# Schematic_Final.net
KiCad netlist of a schematic drawn in EAGLE
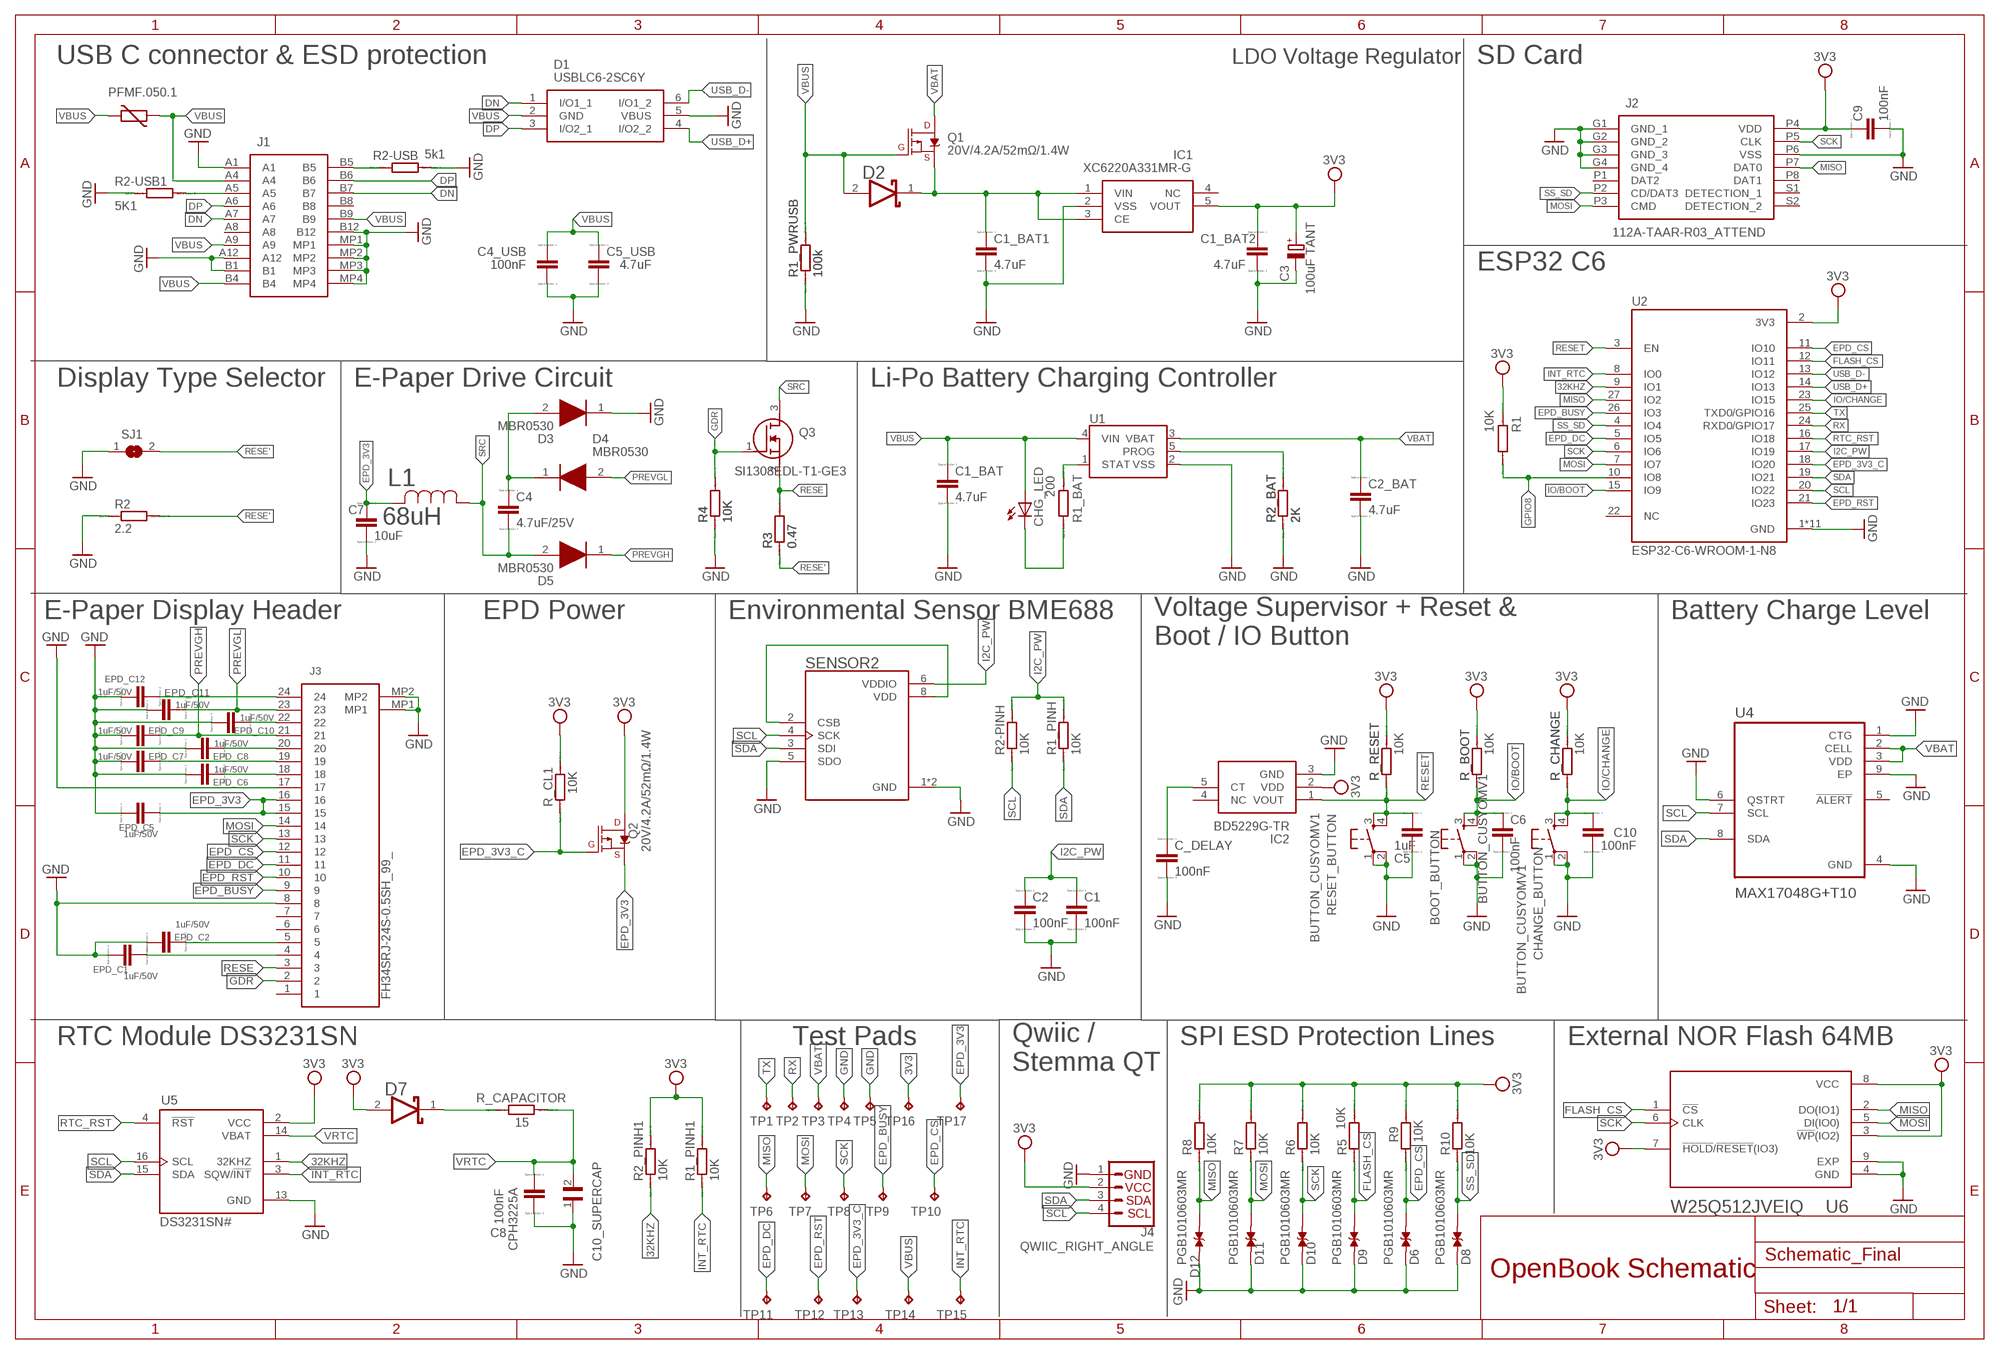
[diagram p0: schematic, sheet 1]

(export (version "E")
  (design (tool "Eeschema 10.0.6"))
  (components
    (comp (ref "BOOT_BUTTON")
      (value "BUTTON_CUSYOMV1")
      (footprint "eagle-import:MYBUTTON")
      (libsource (lib "eagle-import") (part "BUTTON_CUSYOMV1"))
    )
    (comp (ref "C1")
      (value "100nF")
      (footprint "eagle-import:ESP32_WROVER_EAGLE-LTSPICE_C0402")
      (libsource (lib "eagle-import") (part "ESP32_WROVER_EAGLE-LTSPICE_CC0402"))
    )
    (comp (ref "C1_BAT")
      (value "4.7uF")
      (footprint "eagle-import:ESP32_WROVER_EAGLE-LTSPICE_C0402")
      (libsource (lib "eagle-import") (part "ESP32_WROVER_EAGLE-LTSPICE_CC0402"))
    )
    (comp (ref "C1_BAT1")
      (value "4.7uF")
      (footprint "eagle-import:ESP32_WROVER_EAGLE-LTSPICE_C0402")
      (libsource (lib "eagle-import") (part "ESP32_WROVER_EAGLE-LTSPICE_CC0402"))
    )
    (comp (ref "C1_BAT2")
      (value "4.7uF")
      (footprint "eagle-import:ESP32_WROVER_EAGLE-LTSPICE_C0402")
      (libsource (lib "eagle-import") (part "ESP32_WROVER_EAGLE-LTSPICE_CC0402"))
    )
    (comp (ref "C2")
      (value "100nF")
      (footprint "eagle-import:ESP32_WROVER_EAGLE-LTSPICE_C0402")
      (libsource (lib "eagle-import") (part "ESP32_WROVER_EAGLE-LTSPICE_CC0402"))
    )
    (comp (ref "C2_BAT")
      (value "4.7uF")
      (footprint "eagle-import:ESP32_WROVER_EAGLE-LTSPICE_C0402")
      (libsource (lib "eagle-import") (part "ESP32_WROVER_EAGLE-LTSPICE_CC0402"))
    )
    (comp (ref "C3")
      (value "100uF TANT")
      (footprint "eagle-import:RCL_CT3528")
      (libsource (lib "eagle-import") (part "RCL_CPOL-EUCT3528"))
    )
    (comp (ref "C4")
      (value "4.7uF/25V")
      (footprint "eagle-import:ESP32_WROVER_EAGLE-LTSPICE_C0402")
      (libsource (lib "eagle-import") (part "ESP32_WROVER_EAGLE-LTSPICE_CC0402"))
    )
    (comp (ref "C4_USB")
      (value "100nF")
      (footprint "eagle-import:ESP32_WROVER_EAGLE-LTSPICE_C0402")
      (libsource (lib "eagle-import") (part "ESP32_WROVER_EAGLE-LTSPICE_CC0402"))
    )
    (comp (ref "C5")
      (value "1uF")
      (footprint "eagle-import:ESP32_WROVER_EAGLE-LTSPICE_C0402")
      (libsource (lib "eagle-import") (part "ESP32_WROVER_EAGLE-LTSPICE_CC0402"))
    )
    (comp (ref "C5_USB")
      (value "4.7uF")
      (footprint "eagle-import:ESP32_WROVER_EAGLE-LTSPICE_C0402")
      (libsource (lib "eagle-import") (part "ESP32_WROVER_EAGLE-LTSPICE_CC0402"))
    )
    (comp (ref "C6")
      (value "100nF")
      (footprint "eagle-import:ESP32_WROVER_EAGLE-LTSPICE_C0402")
      (libsource (lib "eagle-import") (part "ESP32_WROVER_EAGLE-LTSPICE_CC0402"))
    )
    (comp (ref "C7")
      (value "10uF")
      (footprint "eagle-import:ESP32_WROVER_EAGLE-LTSPICE_C0402")
      (libsource (lib "eagle-import") (part "ESP32_WROVER_EAGLE-LTSPICE_CC0402"))
    )
    (comp (ref "C8")
      (value "100nF")
      (footprint "eagle-import:ESP32_WROVER_EAGLE-LTSPICE_C0402")
      (libsource (lib "eagle-import") (part "ESP32_WROVER_EAGLE-LTSPICE_CC0402"))
    )
    (comp (ref "C9")
      (value "100nF")
      (footprint "eagle-import:ESP32_WROVER_EAGLE-LTSPICE_C0402")
      (libsource (lib "eagle-import") (part "ESP32_WROVER_EAGLE-LTSPICE_CC0402"))
    )
    (comp (ref "C10")
      (value "100nF")
      (footprint "eagle-import:ESP32_WROVER_EAGLE-LTSPICE_C0402")
      (libsource (lib "eagle-import") (part "ESP32_WROVER_EAGLE-LTSPICE_CC0402"))
    )
    (comp (ref "C10_SUPERCAP")
      (value "CPH3225A")
      (footprint "eagle-import:CAPCP3225X100N")
      (fields (field (name "MF") "Seiko Instruments"))
      (libsource (lib "eagle-import") (part "CPH3225A"))
    )
    (comp (ref "CHANGE_BUTTON")
      (value "BUTTON_CUSYOMV1")
      (footprint "eagle-import:MYBUTTON")
      (libsource (lib "eagle-import") (part "BUTTON_CUSYOMV1"))
    )
    (comp (ref "CHG_LED")
      (value "ADAFRUIT_LEDCHIP-LED0603")
      (footprint "eagle-import:ADAFRUIT_CHIP-LED0603")
      (libsource (lib "eagle-import") (part "ADAFRUIT_LEDCHIP-LED0603"))
    )
    (comp (ref "C_DELAY")
      (value "100nF")
      (footprint "eagle-import:ESP32_WROVER_EAGLE-LTSPICE_C0402")
      (libsource (lib "eagle-import") (part "ESP32_WROVER_EAGLE-LTSPICE_CC0402"))
    )
    (comp (ref "D1")
      (value "USBLC6-2SC6Y")
      (footprint "eagle-import:SOT95P280X145-6N")
      (fields (field (name "MF") "STMicroelectronics"))
      (libsource (lib "eagle-import") (part "USBLC6-2SC6Y"))
    )
    (comp (ref "D2")
      (value "ESP32_WROVER_AVX---SD0805S020S1R0_AVX_SD0805S020S1R0_0_0AVX_SD0805S020S1R0_0_0")
      (footprint "eagle-import:ESP32_WROVER_AVX---SD0805S020S1R0_AVX_SD0805S020S1R0_0")
      (fields
        (field (name "DIGIKEY_PART_NUMBER") "478-7800-1-ND")
        (field (name "MF") "AVX")
        (field (name "MOUSER_PART_NUMBER") "581-SD0805S020S1R0")
      )
      (libsource (lib "eagle-import") (part "ESP32_WROVER_AVX---SD0805S020S1R0_AVX_SD0805S020S1R0_0_0AVX_SD0805S020S1R0_0_0"))
    )
    (comp (ref "D3")
      (value "MBR0530")
      (footprint "eagle-import:SOD3716X135N")
      (fields (field (name "MF") "ON Semiconductor"))
      (libsource (lib "eagle-import") (part "MBR0530"))
    )
    (comp (ref "D4")
      (value "MBR0530")
      (footprint "eagle-import:SOD3716X135N")
      (fields (field (name "MF") "ON Semiconductor"))
      (libsource (lib "eagle-import") (part "MBR0530"))
    )
    (comp (ref "D5")
      (value "MBR0530")
      (footprint "eagle-import:SOD3716X135N")
      (fields (field (name "MF") "ON Semiconductor"))
      (libsource (lib "eagle-import") (part "MBR0530"))
    )
    (comp (ref "D6")
      (value "PGB1010603MR")
      (footprint "eagle-import:DIOC1608X36N")
      (fields (field (name "MF") "Littelfuse Inc."))
      (libsource (lib "eagle-import") (part "PGB1010603MR"))
    )
    (comp (ref "D7")
      (value "ESP32_WROVER_AVX---SD0805S020S1R0_AVX_SD0805S020S1R0_0_0AVX_SD0805S020S1R0_0_0")
      (footprint "eagle-import:ESP32_WROVER_AVX---SD0805S020S1R0_AVX_SD0805S020S1R0_0")
      (fields
        (field (name "DIGIKEY_PART_NUMBER") "478-7800-1-ND")
        (field (name "MF") "AVX")
        (field (name "MOUSER_PART_NUMBER") "581-SD0805S020S1R0")
      )
      (libsource (lib "eagle-import") (part "DeskAssistant v19 v1_vf.bE1N5c7jRn-k-Y7_dsTgZA_ESP32_WROVER_AVX---SD0805S020S1R0_AVX_SD0805S020S1R0_0_0AVX_SD0805S020S1R0_0_0"))
    )
    (comp (ref "D8")
      (value "PGB1010603MR")
      (footprint "eagle-import:DIOC1608X36N")
      (fields (field (name "MF") "Littelfuse Inc."))
      (libsource (lib "eagle-import") (part "PGB1010603MR"))
    )
    (comp (ref "D9")
      (value "PGB1010603MR")
      (footprint "eagle-import:DIOC1608X36N")
      (fields (field (name "MF") "Littelfuse Inc."))
      (libsource (lib "eagle-import") (part "PGB1010603MR"))
    )
    (comp (ref "D10")
      (value "PGB1010603MR")
      (footprint "eagle-import:DIOC1608X36N")
      (fields (field (name "MF") "Littelfuse Inc."))
      (libsource (lib "eagle-import") (part "PGB1010603MR"))
    )
    (comp (ref "D11")
      (value "PGB1010603MR")
      (footprint "eagle-import:DIOC1608X36N")
      (fields (field (name "MF") "Littelfuse Inc."))
      (libsource (lib "eagle-import") (part "PGB1010603MR"))
    )
    (comp (ref "D12")
      (value "PGB1010603MR")
      (footprint "eagle-import:DIOC1608X36N")
      (fields (field (name "MF") "Littelfuse Inc."))
      (libsource (lib "eagle-import") (part "PGB1010603MR"))
    )
    (comp (ref "EPD_C1")
      (value "1uF/50V")
      (footprint "eagle-import:ESP32_WROVER_EAGLE-LTSPICE_C0402")
      (libsource (lib "eagle-import") (part "ESP32_WROVER_EAGLE-LTSPICE_CC0402"))
    )
    (comp (ref "EPD_C2")
      (value "1uF/50V")
      (footprint "eagle-import:ESP32_WROVER_EAGLE-LTSPICE_C0402")
      (libsource (lib "eagle-import") (part "ESP32_WROVER_EAGLE-LTSPICE_CC0402"))
    )
    (comp (ref "EPD_C5")
      (value "1uF/50V")
      (footprint "eagle-import:ESP32_WROVER_EAGLE-LTSPICE_C0402")
      (libsource (lib "eagle-import") (part "ESP32_WROVER_EAGLE-LTSPICE_CC0402"))
    )
    (comp (ref "EPD_C6")
      (value "1uF/50V")
      (footprint "eagle-import:ESP32_WROVER_EAGLE-LTSPICE_C0402")
      (libsource (lib "eagle-import") (part "ESP32_WROVER_EAGLE-LTSPICE_CC0402"))
    )
    (comp (ref "EPD_C7")
      (value "1uF/50V")
      (footprint "eagle-import:ESP32_WROVER_EAGLE-LTSPICE_C0402")
      (libsource (lib "eagle-import") (part "ESP32_WROVER_EAGLE-LTSPICE_CC0402"))
    )
    (comp (ref "EPD_C8")
      (value "1uF/50V")
      (footprint "eagle-import:ESP32_WROVER_EAGLE-LTSPICE_C0402")
      (libsource (lib "eagle-import") (part "ESP32_WROVER_EAGLE-LTSPICE_CC0402"))
    )
    (comp (ref "EPD_C9")
      (value "1uF/50V")
      (footprint "eagle-import:ESP32_WROVER_EAGLE-LTSPICE_C0402")
      (libsource (lib "eagle-import") (part "ESP32_WROVER_EAGLE-LTSPICE_CC0402"))
    )
    (comp (ref "EPD_C10")
      (value "1uF/50V")
      (footprint "eagle-import:ESP32_WROVER_EAGLE-LTSPICE_C0402")
      (libsource (lib "eagle-import") (part "ESP32_WROVER_EAGLE-LTSPICE_CC0402"))
    )
    (comp (ref "EPD_C11")
      (value "1uF/50V")
      (footprint "eagle-import:ESP32_WROVER_EAGLE-LTSPICE_C0402")
      (libsource (lib "eagle-import") (part "ESP32_WROVER_EAGLE-LTSPICE_CC0402"))
    )
    (comp (ref "EPD_C12")
      (value "1uF/50V")
      (footprint "eagle-import:ESP32_WROVER_EAGLE-LTSPICE_C0402")
      (libsource (lib "eagle-import") (part "ESP32_WROVER_EAGLE-LTSPICE_CC0402"))
    )
    (comp (ref "IC1")
      (value "XC6220A331MR-G")
      (footprint "eagle-import:SOT95P280X120-5N")
      (fields (field (name "MOUSER_PART_NUMBER") "865-XC6220A331MR-G"))
      (libsource (lib "eagle-import") (part "XC6220A331MR-G"))
    )
    (comp (ref "IC2")
      (value "BD5229G-TR")
      (footprint "eagle-import:SOT95P280X125-5N")
      (fields (field (name "MOUSER_PART_NUMBER") "755-BD5229G-TR"))
      (libsource (lib "eagle-import") (part "BD5229G-TR"))
    )
    (comp (ref "J1")
      (value "SAMACSYS_PARTS_USB4110-GF-A")
      (footprint "eagle-import:SAMACSYS_PARTS_USB4110GFA")
      (fields
        (field (name "MANUFACTURER_PART_NUMBER") "USB4110-GF-A")
        (field (name "MOUSER_PART_NUMBER") "640-USB4110-GF-A")
      )
      (libsource (lib "eagle-import") (part "SAMACSYS_PARTS_USB4110-GF-A"))
    )
    (comp (ref "J2")
      (value "112A-TAAR-R03_ATTEND")
      (footprint "eagle-import:112ATAARR03ATTEND")
      (fields (field (name "MANUFACTURER_PART_NUMBER") "112A-TAAR-R03 ATTEND"))
      (libsource (lib "eagle-import") (part "112A-TAAR-R03_ATTEND"))
    )
    (comp (ref "J3")
      (value "FH34SRJ-24S-0.5SH_99_")
      (footprint "eagle-import:FH34SRJ24S05SH99")
      (fields
        (field (name "MANUFACTURER_PART_NUMBER") "FH34SRJ-24S-0.5SH(99)")
        (field (name "MOUSER_PART_NUMBER") "798-FH34SRJ24S05SH99")
      )
      (libsource (lib "eagle-import") (part "FH34SRJ-24S-0.5SH_99_"))
    )
    (comp (ref "J4")
      (value "QWIIC_RIGHT_ANGLE")
      (footprint "eagle-import:JST04_1MM_RA")
      (libsource (lib "eagle-import") (part "QWIIC_CONNECTORJS-1MM"))
    )
    (comp (ref "L1")
      (value "68uH")
      (footprint "eagle-import:IND_4828-WE-TPC_WRE")
      (fields
        (field (name "MANUFACTURER_PART_NUMBER") "744043680")
        (field (name "COPYRIGHT") "Copyright (C) 2024 Ultra Librarian. All rights reserved.")
      )
      (libsource (lib "eagle-import") (part "744043680IND_4828-WE-TPC_WRE"))
    )
    (comp (ref "PFMF.050.1")
      (value "ESP32C6_VARISTORCN1812")
      (footprint "eagle-import:ESP32C6_VARISTOR_CT_CN1812")
      (libsource (lib "eagle-import") (part "ESP32C6_VARISTORCN1812"))
    )
    (comp (ref "Q1")
      (value "20V/4.2A/52mΩ/1.4W")
      (footprint "eagle-import:ESP32_WROVER_SPARKFUN-DISCRETESEMI_SOT23-3")
      (libsource (lib "eagle-import") (part "ESP32_WROVER_SPARKFUN-DISCRETESEMI_MOSFET_PCH-DMG2305UX-7"))
    )
    (comp (ref "Q2")
      (value "20V/4.2A/52mΩ/1.4W")
      (footprint "eagle-import:ESP32_WROVER_SPARKFUN-DISCRETESEMI_SOT23-3")
      (libsource (lib "eagle-import") (part "ESP32_WROVER_SPARKFUN-DISCRETESEMI_MOSFET_PCH-DMG2305UX-7"))
    )
    (comp (ref "Q3")
      (value "SI1308EDL-T1-GE3")
      (footprint "eagle-import:SOT65P210X110-3N")
      (fields (field (name "MF") "Vishay Siliconix"))
      (libsource (lib "eagle-import") (part "SI1308EDL-T1-GE3"))
    )
    (comp (ref "R1")
      (value "10K")
      (footprint "eagle-import:ESP32_WROVER_EAGLE-LTSPICE_R0402")
      (libsource (lib "eagle-import") (part "DeskAssistant v19 v1_vf.bE1N5c7jRn-k-Y7_dsTgZA_ESP32_WROVER_EAGLE-LTSPICE_RR0402"))
    )
    (comp (ref "R1_BAT")
      (value "200")
      (footprint "eagle-import:ESP32_WROVER_EAGLE-LTSPICE_R0402")
      (libsource (lib "eagle-import") (part "DeskAssistant v19 v1_vf.bE1N5c7jRn-k-Y7_dsTgZA_ESP32_WROVER_EAGLE-LTSPICE_RR0402"))
    )
    (comp (ref "R1_PINH")
      (value "10K")
      (footprint "eagle-import:ESP32_WROVER_EAGLE-LTSPICE_R0402")
      (libsource (lib "eagle-import") (part "DeskAssistant v19 v1_vf.bE1N5c7jRn-k-Y7_dsTgZA_ESP32_WROVER_EAGLE-LTSPICE_RR0402"))
    )
    (comp (ref "R1_PINH1")
      (value "10K")
      (footprint "eagle-import:ESP32_WROVER_EAGLE-LTSPICE_R0402")
      (libsource (lib "eagle-import") (part "DeskAssistant v19 v1_vf.bE1N5c7jRn-k-Y7_dsTgZA_ESP32_WROVER_EAGLE-LTSPICE_RR0402"))
    )
    (comp (ref "R1_PWRUSB")
      (value "100k")
      (footprint "eagle-import:ESP32_WROVER_EAGLE-LTSPICE_R0402")
      (libsource (lib "eagle-import") (part "DeskAssistant v19 v1_vf.bE1N5c7jRn-k-Y7_dsTgZA_ESP32_WROVER_EAGLE-LTSPICE_RR0402"))
    )
    (comp (ref "R2")
      (value "2.2")
      (footprint "eagle-import:ESP32_WROVER_EAGLE-LTSPICE_R0402")
      (libsource (lib "eagle-import") (part "DeskAssistant v19 v1_vf.bE1N5c7jRn-k-Y7_dsTgZA_ESP32_WROVER_EAGLE-LTSPICE_RR0402"))
    )
    (comp (ref "R2-PINH")
      (value "10K")
      (footprint "eagle-import:ESP32_WROVER_EAGLE-LTSPICE_R0402")
      (libsource (lib "eagle-import") (part "DeskAssistant v19 v1_vf.bE1N5c7jRn-k-Y7_dsTgZA_ESP32_WROVER_EAGLE-LTSPICE_RR0402"))
    )
    (comp (ref "R2-USB")
      (value "5k1")
      (footprint "eagle-import:ESP32_WROVER_EAGLE-LTSPICE_R0402")
      (libsource (lib "eagle-import") (part "ESP32_WROVER_EAGLE-LTSPICE_RR0402"))
    )
    (comp (ref "R2-USB1")
      (value "5K1")
      (footprint "eagle-import:ESP32_WROVER_EAGLE-LTSPICE_R0402")
      (libsource (lib "eagle-import") (part "ESP32_WROVER_EAGLE-LTSPICE_RR0402"))
    )
    (comp (ref "R2_BAT")
      (value "2K")
      (footprint "eagle-import:ESP32_WROVER_EAGLE-LTSPICE_R0402")
      (libsource (lib "eagle-import") (part "DeskAssistant v19 v1_vf.bE1N5c7jRn-k-Y7_dsTgZA_ESP32_WROVER_EAGLE-LTSPICE_RR0402"))
    )
    (comp (ref "R2_PINH1")
      (value "10K")
      (footprint "eagle-import:ESP32_WROVER_EAGLE-LTSPICE_R0402")
      (libsource (lib "eagle-import") (part "DeskAssistant v19 v1_vf.bE1N5c7jRn-k-Y7_dsTgZA_ESP32_WROVER_EAGLE-LTSPICE_RR0402"))
    )
    (comp (ref "R3")
      (value "0.47")
      (footprint "eagle-import:ESP32_WROVER_EAGLE-LTSPICE_R0402")
      (libsource (lib "eagle-import") (part "DeskAssistant v19 v1_vf.bE1N5c7jRn-k-Y7_dsTgZA_ESP32_WROVER_EAGLE-LTSPICE_RR0402"))
    )
    (comp (ref "R4")
      (value "10K")
      (footprint "eagle-import:ESP32_WROVER_EAGLE-LTSPICE_R0402")
      (libsource (lib "eagle-import") (part "DeskAssistant v19 v1_vf.bE1N5c7jRn-k-Y7_dsTgZA_ESP32_WROVER_EAGLE-LTSPICE_RR0402"))
    )
    (comp (ref "R5")
      (value "10K")
      (footprint "eagle-import:ESP32_WROVER_EAGLE-LTSPICE_R0402")
      (libsource (lib "eagle-import") (part "DeskAssistant v19 v1_vf.bE1N5c7jRn-k-Y7_dsTgZA_ESP32_WROVER_EAGLE-LTSPICE_RR0402"))
    )
    (comp (ref "R6")
      (value "10K")
      (footprint "eagle-import:ESP32_WROVER_EAGLE-LTSPICE_R0402")
      (libsource (lib "eagle-import") (part "DeskAssistant v19 v1_vf.bE1N5c7jRn-k-Y7_dsTgZA_ESP32_WROVER_EAGLE-LTSPICE_RR0402"))
    )
    (comp (ref "R7")
      (value "10K")
      (footprint "eagle-import:ESP32_WROVER_EAGLE-LTSPICE_R0402")
      (libsource (lib "eagle-import") (part "DeskAssistant v19 v1_vf.bE1N5c7jRn-k-Y7_dsTgZA_ESP32_WROVER_EAGLE-LTSPICE_RR0402"))
    )
    (comp (ref "R8")
      (value "10K")
      (footprint "eagle-import:ESP32_WROVER_EAGLE-LTSPICE_R0402")
      (libsource (lib "eagle-import") (part "DeskAssistant v19 v1_vf.bE1N5c7jRn-k-Y7_dsTgZA_ESP32_WROVER_EAGLE-LTSPICE_RR0402"))
    )
    (comp (ref "R9")
      (value "10K")
      (footprint "eagle-import:ESP32_WROVER_EAGLE-LTSPICE_R0402")
      (libsource (lib "eagle-import") (part "DeskAssistant v19 v1_vf.bE1N5c7jRn-k-Y7_dsTgZA_ESP32_WROVER_EAGLE-LTSPICE_RR0402"))
    )
    (comp (ref "R10")
      (value "10K")
      (footprint "eagle-import:ESP32_WROVER_EAGLE-LTSPICE_R0402")
      (libsource (lib "eagle-import") (part "DeskAssistant v19 v1_vf.bE1N5c7jRn-k-Y7_dsTgZA_ESP32_WROVER_EAGLE-LTSPICE_RR0402"))
    )
    (comp (ref "RESET_BUTTON")
      (value "BUTTON_CUSYOMV1")
      (footprint "eagle-import:MYBUTTON")
      (libsource (lib "eagle-import") (part "BUTTON_CUSYOMV1"))
    )
    (comp (ref "R_BOOT")
      (value "10K")
      (footprint "eagle-import:ESP32_WROVER_EAGLE-LTSPICE_R0402")
      (libsource (lib "eagle-import") (part "DeskAssistant v19 v1_vf.bE1N5c7jRn-k-Y7_dsTgZA_ESP32_WROVER_EAGLE-LTSPICE_RR0402"))
    )
    (comp (ref "R_CAPACITOR")
      (value "15")
      (footprint "eagle-import:ESP32_WROVER_EAGLE-LTSPICE_R0402")
      (libsource (lib "eagle-import") (part "DeskAssistant v19 v1_vf.bE1N5c7jRn-k-Y7_dsTgZA_ESP32_WROVER_EAGLE-LTSPICE_RR0402"))
    )
    (comp (ref "R_CHANGE")
      (value "10K")
      (footprint "eagle-import:ESP32_WROVER_EAGLE-LTSPICE_R0402")
      (libsource (lib "eagle-import") (part "DeskAssistant v19 v1_vf.bE1N5c7jRn-k-Y7_dsTgZA_ESP32_WROVER_EAGLE-LTSPICE_RR0402"))
    )
    (comp (ref "R_CL1")
      (value "10K")
      (footprint "eagle-import:ESP32_WROVER_EAGLE-LTSPICE_R0402")
      (libsource (lib "eagle-import") (part "DeskAssistant v19 v1_vf.bE1N5c7jRn-k-Y7_dsTgZA_ESP32_WROVER_EAGLE-LTSPICE_RR0402"))
    )
    (comp (ref "R_RESET")
      (value "10K")
      (footprint "eagle-import:ESP32_WROVER_EAGLE-LTSPICE_R0402")
      (libsource (lib "eagle-import") (part "DeskAssistant v19 v1_vf.bE1N5c7jRn-k-Y7_dsTgZA_ESP32_WROVER_EAGLE-LTSPICE_RR0402"))
    )
    (comp (ref "SENSOR2")
      (value "ESP32_WROVER_BME680_BME680")
      (footprint "eagle-import:ESP32_WROVER_BME680_PSON80P300X300X100-8N")
      (fields (field (name "MF") "Bosch Sensortec") (field (name "MP") "BME680"))
      (libsource (lib "eagle-import") (part "ESP32_WROVER_BME680_BME680"))
    )
    (comp (ref "SJ1") (value "SJ") (footprint "eagle-import:SJ") (libsource (lib "eagle-import") (part "SJ")))
    (comp (ref "TP1")
      (value "TPTP20R")
      (footprint "eagle-import:TP20R")
      (libsource (lib "eagle-import") (part "TPTP20R"))
    )
    (comp (ref "TP2")
      (value "TPTP20R")
      (footprint "eagle-import:TP20R")
      (libsource (lib "eagle-import") (part "TPTP20R"))
    )
    (comp (ref "TP3")
      (value "TPTP20R")
      (footprint "eagle-import:TP20R")
      (libsource (lib "eagle-import") (part "TPTP20R"))
    )
    (comp (ref "TP4")
      (value "TPTP20R")
      (footprint "eagle-import:TP20R")
      (libsource (lib "eagle-import") (part "TPTP20R"))
    )
    (comp (ref "TP5")
      (value "TPTP20R")
      (footprint "eagle-import:TP20R")
      (libsource (lib "eagle-import") (part "TPTP20R"))
    )
    (comp (ref "TP6")
      (value "TPTP20R")
      (footprint "eagle-import:TP20R")
      (libsource (lib "eagle-import") (part "TPTP20R"))
    )
    (comp (ref "TP7")
      (value "TPTP20R")
      (footprint "eagle-import:TP20R")
      (libsource (lib "eagle-import") (part "TPTP20R"))
    )
    (comp (ref "TP8")
      (value "TPTP20R")
      (footprint "eagle-import:TP20R")
      (libsource (lib "eagle-import") (part "TPTP20R"))
    )
    (comp (ref "TP9")
      (value "TPTP20R")
      (footprint "eagle-import:TP20R")
      (libsource (lib "eagle-import") (part "TPTP20R"))
    )
    (comp (ref "TP10")
      (value "TPTP20R")
      (footprint "eagle-import:TP20R")
      (libsource (lib "eagle-import") (part "TPTP20R"))
    )
    (comp (ref "TP11")
      (value "TPTP20R")
      (footprint "eagle-import:TP20R")
      (libsource (lib "eagle-import") (part "TPTP20R"))
    )
    (comp (ref "TP12")
      (value "TPTP20R")
      (footprint "eagle-import:TP20R")
      (libsource (lib "eagle-import") (part "TPTP20R"))
    )
    (comp (ref "TP13")
      (value "TPTP20R")
      (footprint "eagle-import:TP20R")
      (libsource (lib "eagle-import") (part "TPTP20R"))
    )
    (comp (ref "TP14")
      (value "TPTP20R")
      (footprint "eagle-import:TP20R")
      (libsource (lib "eagle-import") (part "TPTP20R"))
    )
    (comp (ref "TP15")
      (value "TPTP20R")
      (footprint "eagle-import:TP20R")
      (libsource (lib "eagle-import") (part "TPTP20R"))
    )
    (comp (ref "TP16")
      (value "TPTP20R")
      (footprint "eagle-import:TP20R")
      (libsource (lib "eagle-import") (part "TPTP20R"))
    )
    (comp (ref "TP17")
      (value "TPTP20R")
      (footprint "eagle-import:TP20R")
      (libsource (lib "eagle-import") (part "TPTP20R"))
    )
    (comp (ref "U1")
      (value "ESP32_WROVER_SPARKFUN-IC-POWER_MCP73831")
      (footprint "eagle-import:ESP32_WROVER_SPARKFUN-IC-POWER_SOT23-5")
      (libsource (lib "eagle-import") (part "ESP32_WROVER_SPARKFUN-IC-POWER_MCP73831"))
    )
    (comp (ref "U2")
      (value "ESP32-C6-WROOM-1-N8")
      (footprint "eagle-import:XCVR_ESP32-C6-WROOM-1-N8")
      (fields (field (name "MF") "Espressif Systems"))
      (libsource (lib "eagle-import") (part "ESP32-C6-WROOM-1-N8"))
    )
    (comp (ref "U4")
      (value "MAX17048G+T10")
      (footprint "eagle-import:SON50P200X200X80-9N")
      (fields (field (name "MF") "Analog Devices"))
      (libsource (lib "eagle-import") (part "MAX17048G+T10"))
    )
    (comp (ref "U5")
      (value "DS3231SN#")
      (footprint "eagle-import:SOIC127P1032X265-16N")
      (fields (field (name "MF") "Analog Devices"))
      (libsource (lib "eagle-import") (part "DS3231SN#"))
    )
    (comp (ref "U6")
      (value "W25Q512JVEIQ")
      (footprint "eagle-import:SON127P600X800X80-9N")
      (fields (field (name "MF") "Winbond Electronics"))
      (libsource (lib "eagle-import") (part "W25Q512JVEIQ"))
    )
  )
  (nets
    (net (code "1") (name "3V3") (class "Default")
      (node (ref "C1_BAT2") (pin "1") (pinfunction "1_1") (pintype "passive"))
      (node (ref "C3") (pin "+") (pinfunction "+_+") (pintype "passive"))
      (node (ref "C9") (pin "1") (pinfunction "1_1") (pintype "passive"))
      (node (ref "D7") (pin "2") (pinfunction "ANODE_2") (pintype "bidirectional"))
      (node (ref "IC1") (pin "5") (pinfunction "VOUT_5") (pintype "bidirectional"))
      (node (ref "IC2") (pin "2") (pinfunction "VDD_2") (pintype "bidirectional"))
      (node (ref "J2") (pin "P4") (pinfunction "VDD_P4") (pintype "bidirectional"))
      (node (ref "J4") (pin "2") (pinfunction "2_2") (pintype "power_in"))
      (node (ref "Q2") (pin "3") (pinfunction "D_3") (pintype "bidirectional"))
      (node (ref "R1") (pin "2") (pinfunction "2_2") (pintype "passive"))
      (node (ref "R10") (pin "2") (pinfunction "2_2") (pintype "passive"))
      (node (ref "R1_PINH1") (pin "2") (pinfunction "2_2") (pintype "passive"))
      (node (ref "R2_PINH1") (pin "2") (pinfunction "2_2") (pintype "passive"))
      (node (ref "R5") (pin "2") (pinfunction "2_2") (pintype "passive"))
      (node (ref "R6") (pin "2") (pinfunction "2_2") (pintype "passive"))
      (node (ref "R7") (pin "2") (pinfunction "2_2") (pintype "passive"))
      (node (ref "R8") (pin "2") (pinfunction "2_2") (pintype "passive"))
      (node (ref "R9") (pin "2") (pinfunction "2_2") (pintype "passive"))
      (node (ref "R_BOOT") (pin "2") (pinfunction "2_2") (pintype "passive"))
      (node (ref "R_CHANGE") (pin "2") (pinfunction "2_2") (pintype "passive"))
      (node (ref "R_CL1") (pin "2") (pinfunction "2_2") (pintype "passive"))
      (node (ref "R_RESET") (pin "2") (pinfunction "2_2") (pintype "passive"))
      (node (ref "TP16") (pin "TP") (pinfunction "TP_TP") (pintype "input"))
      (node (ref "U2") (pin "2") (pinfunction "3V3_2") (pintype "power_in"))
      (node (ref "U5") (pin "2") (pinfunction "VCC_2") (pintype "power_in"))
      (node (ref "U6") (pin "3") (pinfunction "~{WP}(IO2)_3") (pintype "bidirectional"))
      (node (ref "U6") (pin "7") (pinfunction "~{HOLD}/~{RESET}(IO3)_7") (pintype "bidirectional"))
      (node (ref "U6") (pin "8") (pinfunction "VCC_8") (pintype "power_in"))
    )
    (net (code "2") (name "32KHZ") (class "Default")
      (node (ref "R2_PINH1") (pin "1") (pinfunction "1_1") (pintype "passive"))
      (node (ref "U2") (pin "9") (pinfunction "IO1_9") (pintype "bidirectional"))
      (node (ref "U5") (pin "1") (pinfunction "32KHZ_1") (pintype "output"))
    )
    (net (code "3") (name "DN") (class "Default")
      (node (ref "D1") (pin "1") (pinfunction "I/O1_1_1") (pintype "bidirectional"))
      (node (ref "J1") (pin "A7") (pinfunction "A7_A7") (pintype "bidirectional"))
      (node (ref "J1") (pin "B7") (pinfunction "B7_B7") (pintype "bidirectional"))
    )
    (net (code "4") (name "DP") (class "Default")
      (node (ref "D1") (pin "3") (pinfunction "I/O2_1_3") (pintype "bidirectional"))
      (node (ref "J1") (pin "A6") (pinfunction "A6_A6") (pintype "bidirectional"))
      (node (ref "J1") (pin "B6") (pinfunction "B6_B6") (pintype "bidirectional"))
    )
    (net (code "5") (name "EPD_3V3") (class "Default")
      (node (ref "C7") (pin "1") (pinfunction "1_1") (pintype "passive"))
      (node (ref "EPD_C5") (pin "2") (pinfunction "2_2") (pintype "passive"))
      (node (ref "J3") (pin "15") (pinfunction "15_15") (pintype "bidirectional"))
      (node (ref "J3") (pin "16") (pinfunction "16_16") (pintype "bidirectional"))
      (node (ref "L1") (pin "2") (pinfunction "2_2") (pintype "passive"))
      (node (ref "Q2") (pin "2") (pinfunction "S_2") (pintype "bidirectional"))
      (node (ref "TP17") (pin "TP") (pinfunction "TP_TP") (pintype "input"))
    )
    (net (code "6") (name "EPD_3V3_C") (class "Default")
      (node (ref "Q2") (pin "1") (pinfunction "G_1") (pintype "bidirectional"))
      (node (ref "R_CL1") (pin "1") (pinfunction "1_1") (pintype "passive"))
      (node (ref "TP13") (pin "TP") (pinfunction "TP_TP") (pintype "input"))
      (node (ref "U2") (pin "18") (pinfunction "IO20_18") (pintype "bidirectional"))
    )
    (net (code "7") (name "EPD_BUSY") (class "Default")
      (node (ref "J3") (pin "9") (pinfunction "9_9") (pintype "bidirectional"))
      (node (ref "TP9") (pin "TP") (pinfunction "TP_TP") (pintype "input"))
      (node (ref "U2") (pin "26") (pinfunction "IO3_26") (pintype "bidirectional"))
    )
    (net (code "8") (name "EPD_CS") (class "Default")
      (node (ref "D6") (pin "2") (pinfunction "2_2") (pintype "passive"))
      (node (ref "J3") (pin "12") (pinfunction "12_12") (pintype "bidirectional"))
      (node (ref "R9") (pin "1") (pinfunction "1_1") (pintype "passive"))
      (node (ref "TP10") (pin "TP") (pinfunction "TP_TP") (pintype "input"))
      (node (ref "U2") (pin "11") (pinfunction "IO10_11") (pintype "bidirectional"))
    )
    (net (code "9") (name "EPD_DC") (class "Default")
      (node (ref "J3") (pin "11") (pinfunction "11_11") (pintype "bidirectional"))
      (node (ref "TP11") (pin "TP") (pinfunction "TP_TP") (pintype "input"))
      (node (ref "U2") (pin "5") (pinfunction "IO5_5") (pintype "bidirectional"))
    )
    (net (code "10") (name "EPD_RST") (class "Default")
      (node (ref "J3") (pin "10") (pinfunction "10_10") (pintype "bidirectional"))
      (node (ref "TP12") (pin "TP") (pinfunction "TP_TP") (pintype "input"))
      (node (ref "U2") (pin "21") (pinfunction "IO23_21") (pintype "bidirectional"))
    )
    (net (code "11") (name "FLASH_CS") (class "Default")
      (node (ref "D9") (pin "2") (pinfunction "2_2") (pintype "passive"))
      (node (ref "R5") (pin "1") (pinfunction "1_1") (pintype "passive"))
      (node (ref "U2") (pin "12") (pinfunction "IO11_12") (pintype "bidirectional"))
      (node (ref "U6") (pin "1") (pinfunction "~{CS}_1") (pintype "input"))
    )
    (net (code "12") (name "GDR") (class "Default")
      (node (ref "J3") (pin "2") (pinfunction "2_2") (pintype "bidirectional"))
      (node (ref "Q3") (pin "1") (pinfunction "G_1") (pintype "bidirectional"))
      (node (ref "R4") (pin "2") (pinfunction "2_2") (pintype "passive"))
    )
    (net (code "13") (name "GND") (class "Default")
      (node (ref "BOOT_BUTTON") (pin "1") (pinfunction "1_1") (pintype "passive"))
      (node (ref "BOOT_BUTTON") (pin "2") (pinfunction "2_2") (pintype "passive"))
      (node (ref "C1") (pin "2") (pinfunction "2_2") (pintype "passive"))
      (node (ref "C10") (pin "2") (pinfunction "2_2") (pintype "passive"))
      (node (ref "C10_SUPERCAP") (pin "1") (pinfunction "1_1") (pintype "passive"))
      (node (ref "C1_BAT") (pin "2") (pinfunction "2_2") (pintype "passive"))
      (node (ref "C1_BAT1") (pin "2") (pinfunction "2_2") (pintype "passive"))
      (node (ref "C1_BAT2") (pin "2") (pinfunction "2_2") (pintype "passive"))
      (node (ref "C2") (pin "2") (pinfunction "2_2") (pintype "passive"))
      (node (ref "C2_BAT") (pin "2") (pinfunction "2_2") (pintype "passive"))
      (node (ref "C3") (pin "-") (pinfunction "-_-") (pintype "passive"))
      (node (ref "C4_USB") (pin "2") (pinfunction "2_2") (pintype "passive"))
      (node (ref "C5") (pin "2") (pinfunction "2_2") (pintype "passive"))
      (node (ref "C5_USB") (pin "2") (pinfunction "2_2") (pintype "passive"))
      (node (ref "C6") (pin "2") (pinfunction "2_2") (pintype "passive"))
      (node (ref "C7") (pin "2") (pinfunction "2_2") (pintype "passive"))
      (node (ref "C8") (pin "2") (pinfunction "2_2") (pintype "passive"))
      (node (ref "C9") (pin "2") (pinfunction "2_2") (pintype "passive"))
      (node (ref "CHANGE_BUTTON") (pin "1") (pinfunction "1_1") (pintype "passive"))
      (node (ref "CHANGE_BUTTON") (pin "2") (pinfunction "2_2") (pintype "passive"))
      (node (ref "C_DELAY") (pin "2") (pinfunction "2_2") (pintype "passive"))
      (node (ref "D1") (pin "5") (pinfunction "VBUS_5") (pintype "bidirectional"))
      (node (ref "D10") (pin "1") (pinfunction "1_1") (pintype "passive"))
      (node (ref "D11") (pin "1") (pinfunction "1_1") (pintype "passive"))
      (node (ref "D12") (pin "1") (pinfunction "1_1") (pintype "passive"))
      (node (ref "D3") (pin "1") (pinfunction "K_1") (pintype "bidirectional"))
      (node (ref "D6") (pin "1") (pinfunction "1_1") (pintype "passive"))
      (node (ref "D8") (pin "1") (pinfunction "1_1") (pintype "passive"))
      (node (ref "D9") (pin "1") (pinfunction "1_1") (pintype "passive"))
      (node (ref "EPD_C1") (pin "1") (pinfunction "1_1") (pintype "passive"))
      (node (ref "EPD_C10") (pin "1") (pinfunction "1_1") (pintype "passive"))
      (node (ref "EPD_C11") (pin "1") (pinfunction "1_1") (pintype "passive"))
      (node (ref "EPD_C12") (pin "1") (pinfunction "1_1") (pintype "passive"))
      (node (ref "EPD_C2") (pin "1") (pinfunction "1_1") (pintype "passive"))
      (node (ref "EPD_C5") (pin "1") (pinfunction "1_1") (pintype "passive"))
      (node (ref "EPD_C6") (pin "1") (pinfunction "1_1") (pintype "passive"))
      (node (ref "EPD_C7") (pin "1") (pinfunction "1_1") (pintype "passive"))
      (node (ref "EPD_C8") (pin "1") (pinfunction "1_1") (pintype "passive"))
      (node (ref "EPD_C9") (pin "1") (pinfunction "1_1") (pintype "passive"))
      (node (ref "IC1") (pin "2") (pinfunction "VSS_2") (pintype "bidirectional"))
      (node (ref "IC2") (pin "3") (pinfunction "GND_3") (pintype "bidirectional"))
      (node (ref "J1") (pin "A1") (pinfunction "A1_A1") (pintype "bidirectional"))
      (node (ref "J1") (pin "A12") (pinfunction "A12_A12") (pintype "bidirectional"))
      (node (ref "J1") (pin "B1") (pinfunction "B1_B1") (pintype "bidirectional"))
      (node (ref "J1") (pin "B12") (pinfunction "B12_B12") (pintype "bidirectional"))
      (node (ref "J1") (pin "MP1") (pinfunction "MP1_MP1") (pintype "bidirectional"))
      (node (ref "J1") (pin "MP2") (pinfunction "MP2_MP2") (pintype "bidirectional"))
      (node (ref "J1") (pin "MP3") (pinfunction "MP3_MP3") (pintype "bidirectional"))
      (node (ref "J1") (pin "MP4") (pinfunction "MP4_MP4") (pintype "bidirectional"))
      (node (ref "J2") (pin "G1") (pinfunction "GND_1_G1") (pintype "bidirectional"))
      (node (ref "J2") (pin "G2") (pinfunction "GND_2_G2") (pintype "bidirectional"))
      (node (ref "J2") (pin "G3") (pinfunction "GND_3_G3") (pintype "bidirectional"))
      (node (ref "J2") (pin "G4") (pinfunction "GND_4_G4") (pintype "bidirectional"))
      (node (ref "J2") (pin "P6") (pinfunction "VSS_P6") (pintype "bidirectional"))
      (node (ref "J3") (pin "17") (pinfunction "17_17") (pintype "bidirectional"))
      (node (ref "J3") (pin "8") (pinfunction "8_8") (pintype "bidirectional"))
      (node (ref "J3") (pin "MP1") (pinfunction "MP1_MP1") (pintype "bidirectional"))
      (node (ref "J3") (pin "MP2") (pinfunction "MP2_MP2") (pintype "bidirectional"))
      (node (ref "J4") (pin "1") (pinfunction "1_1") (pintype "power_in"))
      (node (ref "R1_PWRUSB") (pin "1") (pinfunction "1_1") (pintype "passive"))
      (node (ref "R2") (pin "1") (pinfunction "1_1") (pintype "passive"))
      (node (ref "R2-USB") (pin "2") (pinfunction "2_2") (pintype "passive"))
      (node (ref "R2-USB1") (pin "1") (pinfunction "1_1") (pintype "passive"))
      (node (ref "R2_BAT") (pin "1") (pinfunction "1_1") (pintype "passive"))
      (node (ref "R4") (pin "1") (pinfunction "1_1") (pintype "passive"))
      (node (ref "RESET_BUTTON") (pin "1") (pinfunction "1_1") (pintype "passive"))
      (node (ref "RESET_BUTTON") (pin "2") (pinfunction "2_2") (pintype "passive"))
      (node (ref "SENSOR2") (pin "1") (pinfunction "GND_1") (pintype "power_in"))
      (node (ref "SENSOR2") (pin "5") (pinfunction "SDO_5") (pintype "bidirectional"))
      (node (ref "SENSOR2") (pin "7") (pinfunction "GND_7") (pintype "power_in"))
      (node (ref "SJ1") (pin "1") (pinfunction "1_1") (pintype "passive"))
      (node (ref "TP4") (pin "TP") (pinfunction "TP_TP") (pintype "input"))
      (node (ref "TP5") (pin "TP") (pinfunction "TP_TP") (pintype "input"))
      (node (ref "U1") (pin "2") (pinfunction "VSS_2") (pintype "power_in"))
      (node (ref "U2") (pin "1") (pinfunction "GND_1") (pintype "power_in"))
      (node (ref "U2") (pin "28") (pinfunction "GND_28") (pintype "power_in"))
      (node (ref "U2") (pin "29_1") (pinfunction "GND_29_1") (pintype "power_in"))
      (node (ref "U2") (pin "29_2") (pinfunction "GND_29_2") (pintype "power_in"))
      (node (ref "U2") (pin "29_3") (pinfunction "GND_29_3") (pintype "power_in"))
      (node (ref "U2") (pin "29_4") (pinfunction "GND_29_4") (pintype "power_in"))
      (node (ref "U2") (pin "29_5") (pinfunction "GND_29_5") (pintype "power_in"))
      (node (ref "U2") (pin "29_6") (pinfunction "GND_29_6") (pintype "power_in"))
      (node (ref "U2") (pin "29_7") (pinfunction "GND_29_7") (pintype "power_in"))
      (node (ref "U2") (pin "29_8") (pinfunction "GND_29_8") (pintype "power_in"))
      (node (ref "U2") (pin "29_9") (pinfunction "GND_29_9") (pintype "power_in"))
      (node (ref "U4") (pin "1") (pinfunction "CTG_1") (pintype "power_in"))
      (node (ref "U4") (pin "4") (pinfunction "GND_4") (pintype "power_in"))
      (node (ref "U4") (pin "6") (pinfunction "QSTRT_6") (pintype "input"))
      (node (ref "U4") (pin "9") (pinfunction "EP_9") (pintype "power_in"))
      (node (ref "U5") (pin "13") (pinfunction "GND_13") (pintype "power_in"))
      (node (ref "U6") (pin "4") (pinfunction "GND_4") (pintype "power_in"))
      (node (ref "U6") (pin "9") (pinfunction "EXP_9") (pintype "passive"))
    )
    (net (code "14") (name "GPIO8") (class "Default")
      (node (ref "R1") (pin "1") (pinfunction "1_1") (pintype "passive"))
      (node (ref "U2") (pin "10") (pinfunction "IO8_10") (pintype "bidirectional"))
    )
    (net (code "15") (name "I2C_PW") (class "Default")
      (node (ref "C1") (pin "1") (pinfunction "1_1") (pintype "passive"))
      (node (ref "C2") (pin "1") (pinfunction "1_1") (pintype "passive"))
      (node (ref "R1_PINH") (pin "2") (pinfunction "2_2") (pintype "passive"))
      (node (ref "R2-PINH") (pin "2") (pinfunction "2_2") (pintype "passive"))
      (node (ref "SENSOR2") (pin "6") (pinfunction "VDDIO_6") (pintype "power_in"))
      (node (ref "U2") (pin "17") (pinfunction "IO19_17") (pintype "bidirectional"))
    )
    (net (code "16") (name "INT_RTC") (class "Default")
      (node (ref "R1_PINH1") (pin "1") (pinfunction "1_1") (pintype "passive"))
      (node (ref "TP15") (pin "TP") (pinfunction "TP_TP") (pintype "input"))
      (node (ref "U2") (pin "8") (pinfunction "IO0_8") (pintype "bidirectional"))
      (node (ref "U5") (pin "3") (pinfunction "SQW/~{INT}_3") (pintype "output"))
    )
    (net (code "17") (name "IO{slash}BOOT") (class "Default")
      (node (ref "BOOT_BUTTON") (pin "3") (pinfunction "3_3") (pintype "passive"))
      (node (ref "BOOT_BUTTON") (pin "4") (pinfunction "4_4") (pintype "passive"))
      (node (ref "C6") (pin "1") (pinfunction "1_1") (pintype "passive"))
      (node (ref "R_BOOT") (pin "1") (pinfunction "1_1") (pintype "passive"))
      (node (ref "U2") (pin "15") (pinfunction "IO9_15") (pintype "bidirectional"))
    )
    (net (code "18") (name "IO{slash}CHANGE") (class "Default")
      (node (ref "C10") (pin "1") (pinfunction "1_1") (pintype "passive"))
      (node (ref "CHANGE_BUTTON") (pin "3") (pinfunction "3_3") (pintype "passive"))
      (node (ref "CHANGE_BUTTON") (pin "4") (pinfunction "4_4") (pintype "passive"))
      (node (ref "R_CHANGE") (pin "1") (pinfunction "1_1") (pintype "passive"))
      (node (ref "U2") (pin "23") (pinfunction "IO15_23") (pintype "bidirectional"))
    )
    (net (code "19") (name "MISO") (class "Default")
      (node (ref "D12") (pin "2") (pinfunction "2_2") (pintype "passive"))
      (node (ref "J2") (pin "P7") (pinfunction "DAT0_P7") (pintype "bidirectional"))
      (node (ref "R8") (pin "1") (pinfunction "1_1") (pintype "passive"))
      (node (ref "TP6") (pin "TP") (pinfunction "TP_TP") (pintype "input"))
      (node (ref "U2") (pin "27") (pinfunction "IO2_27") (pintype "bidirectional"))
      (node (ref "U6") (pin "2") (pinfunction "DO(IO1)_2") (pintype "bidirectional"))
    )
    (net (code "20") (name "MOSI") (class "Default")
      (node (ref "D11") (pin "2") (pinfunction "2_2") (pintype "passive"))
      (node (ref "J2") (pin "P3") (pinfunction "CMD_P3") (pintype "bidirectional"))
      (node (ref "J3") (pin "14") (pinfunction "14_14") (pintype "bidirectional"))
      (node (ref "R7") (pin "1") (pinfunction "1_1") (pintype "passive"))
      (node (ref "TP7") (pin "TP") (pinfunction "TP_TP") (pintype "input"))
      (node (ref "U2") (pin "7") (pinfunction "IO7_7") (pintype "bidirectional"))
      (node (ref "U6") (pin "5") (pinfunction "DI(IO0)_5") (pintype "bidirectional"))
    )
    (net (code "21") (name "Net-(CHG_LED-PadC)") (class "Default")
      (node (ref "CHG_LED") (pin "C") (pinfunction "C_C") (pintype "passive"))
      (node (ref "R1_BAT") (pin "1") (pinfunction "1_1") (pintype "passive"))
    )
    (net (code "22") (name "Net-(D2-CATHODE)") (class "Default")
      (node (ref "C1_BAT1") (pin "1") (pinfunction "1_1") (pintype "passive"))
      (node (ref "D2") (pin "1") (pinfunction "CATHODE_1") (pintype "bidirectional"))
      (node (ref "IC1") (pin "1") (pinfunction "VIN_1") (pintype "bidirectional"))
      (node (ref "IC1") (pin "3") (pinfunction "CE_3") (pintype "bidirectional"))
      (node (ref "Q1") (pin "2") (pinfunction "S_2") (pintype "bidirectional"))
    )
    (net (code "23") (name "Net-(D3-A)") (class "Default")
      (node (ref "C4") (pin "1") (pinfunction "1_1") (pintype "passive"))
      (node (ref "D3") (pin "2") (pinfunction "A_2") (pintype "bidirectional"))
      (node (ref "D4") (pin "1") (pinfunction "K_1") (pintype "bidirectional"))
    )
    (net (code "24") (name "Net-(D7-CATHODE)") (class "Default")
      (node (ref "D7") (pin "1") (pinfunction "CATHODE_1") (pintype "bidirectional"))
      (node (ref "R_CAPACITOR") (pin "1") (pinfunction "1_1") (pintype "passive"))
    )
    (net (code "25") (name "Net-(EPD_C1-Pad2)") (class "Default")
      (node (ref "EPD_C1") (pin "2") (pinfunction "2_2") (pintype "passive"))
      (node (ref "J3") (pin "4") (pinfunction "4_4") (pintype "bidirectional"))
    )
    (net (code "26") (name "Net-(EPD_C2-Pad2)") (class "Default")
      (node (ref "EPD_C2") (pin "2") (pinfunction "2_2") (pintype "passive"))
      (node (ref "J3") (pin "5") (pinfunction "5_5") (pintype "bidirectional"))
    )
    (net (code "27") (name "Net-(EPD_C6-Pad2)") (class "Default")
      (node (ref "EPD_C6") (pin "2") (pinfunction "2_2") (pintype "passive"))
      (node (ref "J3") (pin "18") (pinfunction "18_18") (pintype "bidirectional"))
    )
    (net (code "28") (name "Net-(EPD_C7-Pad2)") (class "Default")
      (node (ref "EPD_C7") (pin "2") (pinfunction "2_2") (pintype "passive"))
      (node (ref "J3") (pin "19") (pinfunction "19_19") (pintype "bidirectional"))
    )
    (net (code "29") (name "Net-(EPD_C8-Pad2)") (class "Default")
      (node (ref "EPD_C8") (pin "2") (pinfunction "2_2") (pintype "passive"))
      (node (ref "J3") (pin "20") (pinfunction "20_20") (pintype "bidirectional"))
    )
    (net (code "30") (name "Net-(EPD_C10-Pad2)") (class "Default")
      (node (ref "EPD_C10") (pin "2") (pinfunction "2_2") (pintype "passive"))
      (node (ref "J3") (pin "22") (pinfunction "22_22") (pintype "bidirectional"))
    )
    (net (code "31") (name "Net-(EPD_C12-Pad2)") (class "Default")
      (node (ref "EPD_C12") (pin "2") (pinfunction "2_2") (pintype "passive"))
      (node (ref "J3") (pin "24") (pinfunction "24_24") (pintype "bidirectional"))
    )
    (net (code "32") (name "Net-(IC2-CT)") (class "Default")
      (node (ref "C_DELAY") (pin "1") (pinfunction "1_1") (pintype "passive"))
      (node (ref "IC2") (pin "5") (pinfunction "CT_5") (pintype "bidirectional"))
    )
    (net (code "33") (name "Net-(J1-PadA5)") (class "Default")
      (node (ref "J1") (pin "A5") (pinfunction "A5_A5") (pintype "bidirectional"))
      (node (ref "R2-USB1") (pin "2") (pinfunction "2_2") (pintype "passive"))
    )
    (net (code "34") (name "Net-(J1-PadB5)") (class "Default")
      (node (ref "J1") (pin "B5") (pinfunction "B5_B5") (pintype "bidirectional"))
      (node (ref "R2-USB") (pin "1") (pinfunction "1_1") (pintype "passive"))
    )
    (net (code "35") (name "Net-(SENSOR2-CSB)") (class "Default")
      (node (ref "SENSOR2") (pin "2") (pinfunction "CSB_2") (pintype "input"))
      (node (ref "SENSOR2") (pin "8") (pinfunction "VDD_8") (pintype "power_in"))
    )
    (net (code "36") (name "Net-(U1-PROG)") (class "Default")
      (node (ref "R2_BAT") (pin "2") (pinfunction "2_2") (pintype "passive"))
      (node (ref "U1") (pin "5") (pinfunction "PROG_5") (pintype "input"))
    )
    (net (code "37") (name "Net-(U1-STAT)") (class "Default")
      (node (ref "R1_BAT") (pin "2") (pinfunction "2_2") (pintype "passive"))
      (node (ref "U1") (pin "1") (pinfunction "STAT_1") (pintype "output"))
    )
    (net (code "38") (name "PREVGH") (class "Default")
      (node (ref "D5") (pin "1") (pinfunction "K_1") (pintype "bidirectional"))
      (node (ref "EPD_C9") (pin "2") (pinfunction "2_2") (pintype "passive"))
      (node (ref "J3") (pin "21") (pinfunction "21_21") (pintype "bidirectional"))
    )
    (net (code "39") (name "PREVGL") (class "Default")
      (node (ref "D4") (pin "2") (pinfunction "A_2") (pintype "bidirectional"))
      (node (ref "EPD_C11") (pin "2") (pinfunction "2_2") (pintype "passive"))
      (node (ref "J3") (pin "23") (pinfunction "23_23") (pintype "bidirectional"))
    )
    (net (code "40") (name "RESE") (class "Default")
      (node (ref "J3") (pin "3") (pinfunction "3_3") (pintype "bidirectional"))
      (node (ref "Q3") (pin "2") (pinfunction "S_2") (pintype "bidirectional"))
      (node (ref "R3") (pin "2") (pinfunction "2_2") (pintype "passive"))
    )
    (net (code "41") (name "RESE'") (class "Default")
      (node (ref "R2") (pin "2") (pinfunction "2_2") (pintype "passive"))
      (node (ref "R3") (pin "1") (pinfunction "1_1") (pintype "passive"))
      (node (ref "SJ1") (pin "2") (pinfunction "2_2") (pintype "passive"))
    )
    (net (code "42") (name "RESET") (class "Default")
      (node (ref "C5") (pin "1") (pinfunction "1_1") (pintype "passive"))
      (node (ref "IC2") (pin "1") (pinfunction "VOUT_1") (pintype "bidirectional"))
      (node (ref "RESET_BUTTON") (pin "3") (pinfunction "3_3") (pintype "passive"))
      (node (ref "RESET_BUTTON") (pin "4") (pinfunction "4_4") (pintype "passive"))
      (node (ref "R_RESET") (pin "1") (pinfunction "1_1") (pintype "passive"))
      (node (ref "U2") (pin "3") (pinfunction "EN_3") (pintype "input"))
    )
    (net (code "43") (name "RTC_RST") (class "Default")
      (node (ref "U2") (pin "16") (pinfunction "IO18_16") (pintype "bidirectional"))
      (node (ref "U5") (pin "4") (pinfunction "~{RST}_4") (pintype "input"))
    )
    (net (code "44") (name "RX") (class "Default")
      (node (ref "TP2") (pin "TP") (pinfunction "TP_TP") (pintype "input"))
      (node (ref "U2") (pin "24") (pinfunction "RXD0/GPIO17_24") (pintype "bidirectional"))
    )
    (net (code "45") (name "SCK") (class "Default")
      (node (ref "D10") (pin "2") (pinfunction "2_2") (pintype "passive"))
      (node (ref "J2") (pin "P5") (pinfunction "CLK_P5") (pintype "bidirectional"))
      (node (ref "J3") (pin "13") (pinfunction "13_13") (pintype "bidirectional"))
      (node (ref "R6") (pin "1") (pinfunction "1_1") (pintype "passive"))
      (node (ref "TP8") (pin "TP") (pinfunction "TP_TP") (pintype "input"))
      (node (ref "U2") (pin "6") (pinfunction "IO6_6") (pintype "bidirectional"))
      (node (ref "U6") (pin "6") (pinfunction "CLK_6") (pintype "input"))
    )
    (net (code "46") (name "SCL") (class "Default")
      (node (ref "J4") (pin "4") (pinfunction "4_4") (pintype "passive"))
      (node (ref "R2-PINH") (pin "1") (pinfunction "1_1") (pintype "passive"))
      (node (ref "SENSOR2") (pin "4") (pinfunction "SCK_4") (pintype "input"))
      (node (ref "U2") (pin "20") (pinfunction "IO22_20") (pintype "bidirectional"))
      (node (ref "U4") (pin "7") (pinfunction "SCL_7") (pintype "input"))
      (node (ref "U5") (pin "16") (pinfunction "SCL_16") (pintype "input"))
    )
    (net (code "47") (name "SDA") (class "Default")
      (node (ref "J4") (pin "3") (pinfunction "3_3") (pintype "passive"))
      (node (ref "R1_PINH") (pin "1") (pinfunction "1_1") (pintype "passive"))
      (node (ref "SENSOR2") (pin "3") (pinfunction "SDI_3") (pintype "bidirectional"))
      (node (ref "U2") (pin "19") (pinfunction "IO21_19") (pintype "bidirectional"))
      (node (ref "U4") (pin "8") (pinfunction "SDA_8") (pintype "bidirectional"))
      (node (ref "U5") (pin "15") (pinfunction "SDA_15") (pintype "bidirectional"))
    )
    (net (code "48") (name "SRC") (class "Default")
      (node (ref "C4") (pin "2") (pinfunction "2_2") (pintype "passive"))
      (node (ref "D5") (pin "2") (pinfunction "A_2") (pintype "bidirectional"))
      (node (ref "L1") (pin "1") (pinfunction "1_1") (pintype "passive"))
      (node (ref "Q3") (pin "3") (pinfunction "D_3") (pintype "bidirectional"))
    )
    (net (code "49") (name "SS_SD") (class "Default")
      (node (ref "D8") (pin "2") (pinfunction "2_2") (pintype "passive"))
      (node (ref "J2") (pin "P2") (pinfunction "CD/DAT3_P2") (pintype "bidirectional"))
      (node (ref "R10") (pin "1") (pinfunction "1_1") (pintype "passive"))
      (node (ref "U2") (pin "4") (pinfunction "IO4_4") (pintype "bidirectional"))
    )
    (net (code "50") (name "TX") (class "Default")
      (node (ref "TP1") (pin "TP") (pinfunction "TP_TP") (pintype "input"))
      (node (ref "U2") (pin "25") (pinfunction "TXD0/GPIO16_25") (pintype "bidirectional"))
    )
    (net (code "51") (name "USB_D+") (class "Default")
      (node (ref "D1") (pin "4") (pinfunction "I/O2_2_4") (pintype "bidirectional"))
      (node (ref "U2") (pin "14") (pinfunction "IO13_14") (pintype "bidirectional"))
    )
    (net (code "52") (name "USB_D-") (class "Default")
      (node (ref "D1") (pin "6") (pinfunction "I/O1_2_6") (pintype "bidirectional"))
      (node (ref "U2") (pin "13") (pinfunction "IO12_13") (pintype "bidirectional"))
    )
    (net (code "53") (name "VBAT") (class "Default")
      (node (ref "C2_BAT") (pin "1") (pinfunction "1_1") (pintype "passive"))
      (node (ref "Q1") (pin "3") (pinfunction "D_3") (pintype "bidirectional"))
      (node (ref "TP3") (pin "TP") (pinfunction "TP_TP") (pintype "input"))
      (node (ref "U1") (pin "3") (pinfunction "VBAT_3") (pintype "power_in"))
      (node (ref "U4") (pin "2") (pinfunction "CELL_2") (pintype "power_in"))
      (node (ref "U4") (pin "3") (pinfunction "VDD_3") (pintype "power_in"))
    )
    (net (code "54") (name "VBUS") (class "Default")
      (node (ref "C1_BAT") (pin "1") (pinfunction "1_1") (pintype "passive"))
      (node (ref "C4_USB") (pin "1") (pinfunction "1_1") (pintype "passive"))
      (node (ref "C5_USB") (pin "1") (pinfunction "1_1") (pintype "passive"))
      (node (ref "CHG_LED") (pin "A") (pinfunction "A_A") (pintype "passive"))
      (node (ref "D1") (pin "2") (pinfunction "GND_2") (pintype "bidirectional"))
      (node (ref "D2") (pin "2") (pinfunction "ANODE_2") (pintype "bidirectional"))
      (node (ref "J1") (pin "A4") (pinfunction "A4_A4") (pintype "bidirectional"))
      (node (ref "J1") (pin "A9") (pinfunction "A9_A9") (pintype "bidirectional"))
      (node (ref "J1") (pin "B4") (pinfunction "B4_B4") (pintype "bidirectional"))
      (node (ref "J1") (pin "B9") (pinfunction "B9_B9") (pintype "bidirectional"))
      (node (ref "PFMF.050.1") (pin "1") (pinfunction "1_1") (pintype "passive"))
      (node (ref "PFMF.050.1") (pin "2") (pinfunction "2_2") (pintype "passive"))
      (node (ref "Q1") (pin "1") (pinfunction "G_1") (pintype "bidirectional"))
      (node (ref "R1_PWRUSB") (pin "2") (pinfunction "2_2") (pintype "passive"))
      (node (ref "TP14") (pin "TP") (pinfunction "TP_TP") (pintype "input"))
      (node (ref "U1") (pin "4") (pinfunction "VIN_4") (pintype "power_in"))
    )
    (net (code "55") (name "VRTC") (class "Default")
      (node (ref "C10_SUPERCAP") (pin "2") (pinfunction "2_2") (pintype "passive"))
      (node (ref "C8") (pin "1") (pinfunction "1_1") (pintype "passive"))
      (node (ref "R_CAPACITOR") (pin "2") (pinfunction "2_2") (pintype "passive"))
      (node (ref "U5") (pin "14") (pinfunction "VBAT_14") (pintype "power_in"))
    )
    (net (code "56") (name "unconnected-(IC1-NC-Pad4)") (class "Default")
      (node (ref "IC1") (pin "4") (pinfunction "NC_4") (pintype "no_connect"))
    )
    (net (code "57") (name "unconnected-(IC2-NC-Pad4)") (class "Default")
      (node (ref "IC2") (pin "4") (pinfunction "NC_4") (pintype "no_connect"))
    )
    (net (code "58") (name "unconnected-(J1-PadA8)") (class "Default")
      (node (ref "J1") (pin "A8") (pinfunction "A8_A8") (pintype "bidirectional"))
    )
    (net (code "59") (name "unconnected-(J1-PadB8)") (class "Default")
      (node (ref "J1") (pin "B8") (pinfunction "B8_B8") (pintype "bidirectional"))
    )
    (net (code "60") (name "unconnected-(J2-DAT1-PadP8)") (class "Default")
      (node (ref "J2") (pin "P8") (pinfunction "DAT1_P8") (pintype "bidirectional"))
    )
    (net (code "61") (name "unconnected-(J2-DAT2-PadP1)") (class "Default")
      (node (ref "J2") (pin "P1") (pinfunction "DAT2_P1") (pintype "bidirectional"))
    )
    (net (code "62") (name "unconnected-(J2-DETECTION_1-PadS1)") (class "Default")
      (node (ref "J2") (pin "S1") (pinfunction "DETECTION_1_S1") (pintype "bidirectional"))
    )
    (net (code "63") (name "unconnected-(J2-DETECTION_2-PadS2)") (class "Default")
      (node (ref "J2") (pin "S2") (pinfunction "DETECTION_2_S2") (pintype "bidirectional"))
    )
    (net (code "64") (name "unconnected-(J3-Pad1)") (class "Default")
      (node (ref "J3") (pin "1") (pinfunction "1_1") (pintype "bidirectional"))
    )
    (net (code "65") (name "unconnected-(J3-Pad6)") (class "Default")
      (node (ref "J3") (pin "6") (pinfunction "6_6") (pintype "bidirectional"))
    )
    (net (code "66") (name "unconnected-(J3-Pad7)") (class "Default")
      (node (ref "J3") (pin "7") (pinfunction "7_7") (pintype "bidirectional"))
    )
    (net (code "67") (name "unconnected-(U2-NC-Pad22)") (class "Default")
      (node (ref "U2") (pin "22") (pinfunction "NC_22") (pintype "no_connect"))
    )
    (net (code "68") (name "unconnected-(U4-~{ALERT}-Pad5)") (class "Default")
      (node (ref "U4") (pin "5") (pinfunction "~{ALERT}_5") (pintype "output"))
    )
  )
)
